# Logic_Module_V3.net
KiCad netlist of a schematic drawn in EAGLE
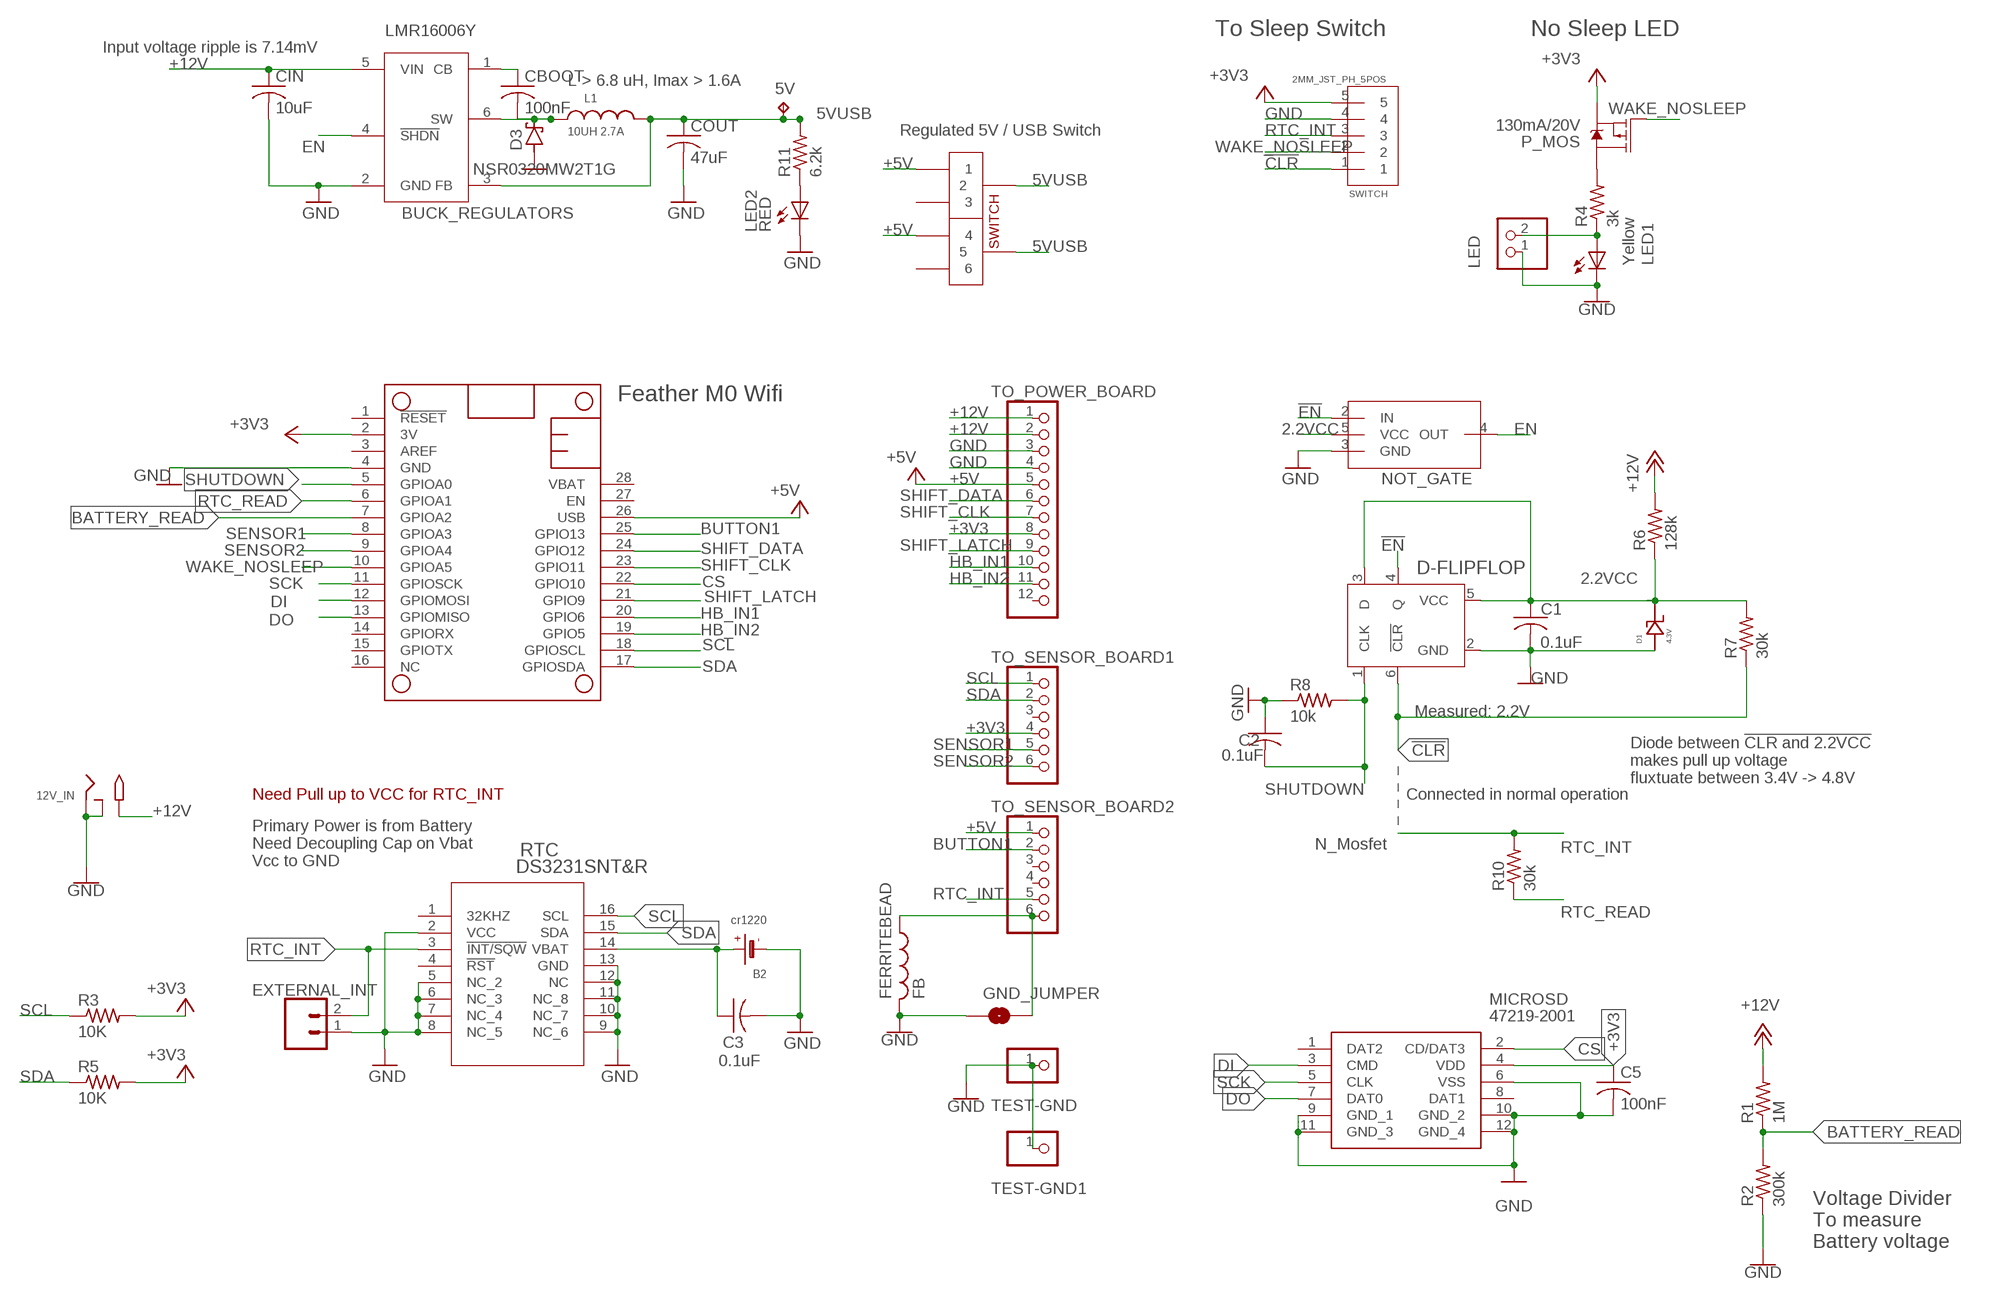
[diagram p0: schematic, sheet 1]

(export (version "E")
  (design (tool "Eeschema 10.0.6"))
  (components
    (comp (ref "5V")
      (value "TPTP16R")
      (footprint "eagle-import:TP16R")
      (libsource (lib "eagle-import") (part "TPTP16R"))
    )
    (comp (ref "12V_IN")
      (value "2.1MMJACKSMT")
      (footprint "eagle-import:DCJACK_2MM_SMT")
      (libsource (lib "eagle-import") (part "2.1MMJACKSMT"))
    )
    (comp (ref "B2")
      (value "cr1220")
      (footprint "eagle-import:CR1220-2")
      (libsource (lib "eagle-import") (part "BATTERYCR1220_2"))
    )
    (comp (ref "C1")
      (value "0.1uF")
      (footprint "eagle-import:C1206")
      (libsource (lib "eagle-import") (part "C-USC1206"))
    )
    (comp (ref "C2")
      (value "0.1uF")
      (footprint "eagle-import:C1206")
      (libsource (lib "eagle-import") (part "C-USC1206"))
    )
    (comp (ref "C3")
      (value "0.1uF")
      (footprint "eagle-import:C1206")
      (libsource (lib "eagle-import") (part "C-USC1206"))
    )
    (comp (ref "C5")
      (value "100nF")
      (footprint "eagle-import:C1206")
      (libsource (lib "eagle-import") (part "resistor_348_C-USC1206"))
    )
    (comp (ref "CBOOT")
      (value "100nF")
      (footprint "eagle-import:C1206")
      (libsource (lib "eagle-import") (part "rcl_334_C-USC1206"))
    )
    (comp (ref "CIN")
      (value "10uF")
      (footprint "eagle-import:C1206K")
      (libsource (lib "eagle-import") (part "rcl_334_C-USC1206K"))
    )
    (comp (ref "COUT")
      (value "47uF")
      (footprint "eagle-import:C1206")
      (libsource (lib "eagle-import") (part "rcl_334_C-USC1206"))
    )
    (comp (ref "D-FLIPFLOP")
      (value "SN74LVC1G175DBVR")
      (footprint "eagle-import:DBV6")
      (libsource (lib "eagle-import") (part "SN74LVC1G175DBVR"))
    )
    (comp (ref "D1")
      (value "4.3V")
      (footprint "eagle-import:DO-219AC")
      (libsource (lib "eagle-import") (part "ZENER-DO219"))
    )
    (comp (ref "D3")
      (value "NSR0320MW2T1G")
      (footprint "eagle-import:SOD323_ST")
      (libsource (lib "eagle-import") (part "BAT60J"))
    )
    (comp (ref "EXTERNAL_INT")
      (value "CONN_021X02_NO_SILK")
      (footprint "eagle-import:1X02_NO_SILK")
      (libsource (lib "eagle-import") (part "CONN_021X02_NO_SILK"))
    )
    (comp (ref "FERRITEBEAD")
      (value "FB")
      (footprint "eagle-import:FB")
      (libsource (lib "eagle-import") (part "FB"))
    )
    (comp (ref "GND_JUMPER")
      (value "JUMPER-SMT_2_NO_NO-SILK")
      (footprint "eagle-import:SMT-JUMPER_2_NO_NO-SILK")
      (libsource (lib "eagle-import") (part "JUMPER-SMT_2_NO_NO-SILK"))
    )
    (comp (ref "L1")
      (value "10UH 2.7A")
      (footprint "eagle-import:WE-MAPI_40XX")
      (libsource (lib "eagle-import") (part "WE-MAPI_4030_74438357100"))
    )
    (comp (ref "LED")
      (value "2.5MM_JST_UP_2POS")
      (footprint "eagle-import:JST_2POS_2.5MM_UP")
      (libsource (lib "eagle-import") (part "2.5MM_JST_UP_2POS"))
    )
    (comp (ref "LED1")
      (value "Yellow")
      (footprint "eagle-import:CHIPLED_0805")
      (libsource (lib "eagle-import") (part "LEDCHIPLED_0805"))
    )
    (comp (ref "LED2")
      (value "RED")
      (footprint "eagle-import:CHIPLED_0805")
      (libsource (lib "eagle-import") (part "LEDCHIPLED_0805"))
    )
    (comp (ref "MICROSD")
      (value "47219-2001")
      (footprint "eagle-import:472192001")
      (fields (field (name "MOUSER_PART_NUMBER") "538-47219-2001"))
      (libsource (lib "eagle-import") (part "47219-2001"))
    )
    (comp (ref "MS1")
      (value "FEATHERWING")
      (footprint "eagle-import:FEATHERWING")
      (libsource (lib "eagle-import") (part "FEATHERWING"))
    )
    (comp (ref "P_MOS")
      (value "130mA/20V")
      (footprint "eagle-import:SOT23-3")
      (libsource (lib "eagle-import") (part "MOSFET_PCH-IRLML2244"))
    )
    (comp (ref "R1")
      (value "1M")
      (footprint "eagle-import:R1206")
      (libsource (lib "eagle-import") (part "R-US_R1206"))
    )
    (comp (ref "R2")
      (value "300k")
      (footprint "eagle-import:R1206")
      (libsource (lib "eagle-import") (part "R-US_R1206"))
    )
    (comp (ref "R3")
      (value "10K")
      (footprint "eagle-import:R1206")
      (libsource (lib "eagle-import") (part "rcl_334_R-US_R1206"))
    )
    (comp (ref "R4")
      (value "3k")
      (footprint "eagle-import:R1206")
      (libsource (lib "eagle-import") (part "resistor_348_R-US_R1206"))
    )
    (comp (ref "R5")
      (value "10K")
      (footprint "eagle-import:R1206")
      (libsource (lib "eagle-import") (part "rcl_334_R-US_R1206"))
    )
    (comp (ref "R6")
      (value "128k")
      (footprint "eagle-import:R1206")
      (libsource (lib "eagle-import") (part "R-US_R1206"))
    )
    (comp (ref "R7")
      (value "30k")
      (footprint "eagle-import:R1206")
      (libsource (lib "eagle-import") (part "R-US_R1206"))
    )
    (comp (ref "R8")
      (value "10k")
      (footprint "eagle-import:R1206")
      (libsource (lib "eagle-import") (part "R-US_R1206"))
    )
    (comp (ref "R10")
      (value "30k")
      (footprint "eagle-import:R1206")
      (libsource (lib "eagle-import") (part "R-US_R1206"))
    )
    (comp (ref "R11")
      (value "6.2k")
      (footprint "eagle-import:RES_1206")
      (fields
        (field (name "DIGIKEY_PART_NUMBER") "WSLP-.05TR-ND")
        (field (name "MANUFACTURER") "Vishay Dale")
        (field (name "MPN") "WSLP1206R0500FEA")
        (field (name "CREATED_BY") "PCBLayout.com")
      )
      (libsource (lib "eagle-import") (part "WSLP1206R0500FEA"))
    )
    (comp (ref "RTC")
      (value "DS3231SNT&R")
      (footprint "eagle-import:21-0042B_16")
      (fields (field (name "MANUFACTURER_PART_NUMBER") "DS3231SN#T&R"))
      (libsource (lib "eagle-import") (part "DS3231SNT&R"))
    )
    (comp (ref "SWITCH")
      (value "2MM_JST_PH_5POS")
      (footprint "eagle-import:2MM_5POS_HEADER")
      (libsource (lib "eagle-import") (part "2MM_JST_PH_5POS"))
    )
    (comp (ref "TEST-GND")
      (value "PINHD-1X1")
      (footprint "eagle-import:1X01")
      (libsource (lib "eagle-import") (part "PINHD-1X1"))
    )
    (comp (ref "TEST-GND1")
      (value "PINHD-1X1")
      (footprint "eagle-import:1X01")
      (libsource (lib "eagle-import") (part "PINHD-1X1"))
    )
    (comp (ref "TO_POWER_BOARD")
      (value "PINHD-1X12")
      (footprint "eagle-import:1X12")
      (libsource (lib "eagle-import") (part "PINHD-1X12"))
    )
    (comp (ref "TO_SENSOR_BOARD1")
      (value "PINHD-1X6CB")
      (footprint "eagle-import:1X06-CLEANBIG")
      (libsource (lib "eagle-import") (part "PINHD-1X6CB"))
    )
    (comp (ref "TO_SENSOR_BOARD2")
      (value "PINHD-1X6CB")
      (footprint "eagle-import:1X06-CLEANBIG")
      (libsource (lib "eagle-import") (part "PINHD-1X6CB"))
    )
    (comp (ref "U$1")
      (value "2PDT_SWITCHJS-SMD")
      (footprint "eagle-import:JS-DPDT-SMD")
      (libsource (lib "eagle-import") (part "2PDT_SWITCHJS-SMD"))
    )
    (comp (ref "U$3")
      (value "NOT_GATE")
      (footprint "eagle-import:SOT753")
      (libsource (lib "eagle-import") (part "NOT_GATE"))
    )
    (comp (ref "VREG")
      (value "BUCK_REGULATORS")
      (footprint "eagle-import:SOT23-6")
      (libsource (lib "eagle-import") (part "BUCK_REGULATORS"))
    )
  )
  (nets
    (net (code "1") (name "+3V3") (class "Default")
      (node (ref "C5") (pin "1") (pinfunction "1_1") (pintype "passive"))
      (node (ref "MICROSD") (pin "4") (pinfunction "VDD_4") (pintype "bidirectional"))
      (node (ref "MS1") (pin "2") (pinfunction "3V_2") (pintype "power_in"))
      (node (ref "P_MOS") (pin "2") (pinfunction "S_2") (pintype "bidirectional"))
      (node (ref "R3") (pin "2") (pinfunction "2_2") (pintype "passive"))
      (node (ref "R5") (pin "2") (pinfunction "2_2") (pintype "passive"))
      (node (ref "SWITCH") (pin "5") (pinfunction "5_5") (pintype "bidirectional"))
      (node (ref "TO_POWER_BOARD") (pin "8") (pinfunction "8_8") (pintype "passive"))
      (node (ref "TO_SENSOR_BOARD1") (pin "4") (pinfunction "4_4") (pintype "passive"))
    )
    (net (code "2") (name "+5V") (class "Default")
      (node (ref "MS1") (pin "26") (pinfunction "USB_26") (pintype "power_in"))
      (node (ref "TO_POWER_BOARD") (pin "5") (pinfunction "5_5") (pintype "passive"))
      (node (ref "TO_SENSOR_BOARD2") (pin "1") (pinfunction "1_1") (pintype "passive"))
      (node (ref "U$1") (pin "P$1") (pinfunction "1_P$1") (pintype "bidirectional"))
      (node (ref "U$1") (pin "P$4") (pinfunction "4_P$4") (pintype "bidirectional"))
    )
    (net (code "3") (name "+12V") (class "Default")
      (node (ref "12V_IN") (pin "PWR2") (pinfunction "TIP_PWR2") (pintype "bidirectional"))
      (node (ref "CIN") (pin "1") (pinfunction "1_1") (pintype "passive"))
      (node (ref "R1") (pin "2") (pinfunction "2_2") (pintype "passive"))
      (node (ref "R6") (pin "2") (pinfunction "2_2") (pintype "passive"))
      (node (ref "TO_POWER_BOARD") (pin "1") (pinfunction "1_1") (pintype "passive"))
      (node (ref "TO_POWER_BOARD") (pin "2") (pinfunction "2_2") (pintype "passive"))
      (node (ref "VREG") (pin "5") (pinfunction "VIN_5") (pintype "bidirectional"))
    )
    (net (code "4") (name "/2.2VCC") (class "Default")
      (node (ref "C1") (pin "1") (pinfunction "1_1") (pintype "passive"))
      (node (ref "D-FLIPFLOP") (pin "3") (pinfunction "D_3") (pintype "input"))
      (node (ref "D-FLIPFLOP") (pin "5") (pinfunction "VCC_5") (pintype "power_in"))
      (node (ref "D1") (pin "FNT") (pinfunction "FNT_FNT") (pintype "bidirectional"))
      (node (ref "R6") (pin "1") (pinfunction "1_1") (pintype "passive"))
      (node (ref "R7") (pin "2") (pinfunction "2_2") (pintype "passive"))
      (node (ref "U$3") (pin "5") (pinfunction "VCC_5") (pintype "bidirectional"))
    )
    (net (code "5") (name "/5VUSB") (class "Default")
      (node (ref "5V") (pin "TP") (pinfunction "TP_TP") (pintype "input"))
      (node (ref "COUT") (pin "1") (pinfunction "1_1") (pintype "passive"))
      (node (ref "L1") (pin "2") (pinfunction "2_2") (pintype "passive"))
      (node (ref "R11") (pin "2") (pinfunction "2_2") (pintype "passive"))
      (node (ref "U$1") (pin "P$2") (pinfunction "2_P$2") (pintype "bidirectional"))
      (node (ref "U$1") (pin "P$5") (pinfunction "5_P$5") (pintype "bidirectional"))
      (node (ref "VREG") (pin "3") (pinfunction "FB_3") (pintype "bidirectional"))
    )
    (net (code "6") (name "/BUTTON1") (class "Default")
      (node (ref "MS1") (pin "25") (pinfunction "GPIO13_25") (pintype "bidirectional"))
      (node (ref "TO_SENSOR_BOARD2") (pin "2") (pinfunction "2_2") (pintype "passive"))
    )
    (net (code "7") (name "/EN") (class "Default")
      (node (ref "U$3") (pin "4") (pinfunction "OUT_4") (pintype "bidirectional"))
      (node (ref "VREG") (pin "4") (pinfunction "~{SHDN}_4") (pintype "bidirectional"))
    )
    (net (code "8") (name "/HB_IN1") (class "Default")
      (node (ref "MS1") (pin "20") (pinfunction "GPIO6_20") (pintype "bidirectional"))
      (node (ref "TO_POWER_BOARD") (pin "10") (pinfunction "10_10") (pintype "passive"))
    )
    (net (code "9") (name "/HB_IN2") (class "Default")
      (node (ref "MS1") (pin "19") (pinfunction "GPIO5_19") (pintype "bidirectional"))
      (node (ref "TO_POWER_BOARD") (pin "11") (pinfunction "11_11") (pintype "passive"))
    )
    (net (code "10") (name "/SENSOR1") (class "Default")
      (node (ref "MS1") (pin "8") (pinfunction "GPIOA3_8") (pintype "bidirectional"))
      (node (ref "TO_SENSOR_BOARD1") (pin "5") (pinfunction "5_5") (pintype "passive"))
    )
    (net (code "11") (name "/SENSOR2") (class "Default")
      (node (ref "MS1") (pin "9") (pinfunction "GPIOA4_9") (pintype "bidirectional"))
      (node (ref "TO_SENSOR_BOARD1") (pin "6") (pinfunction "6_6") (pintype "passive"))
    )
    (net (code "12") (name "/SHIFT_CLK") (class "Default")
      (node (ref "MS1") (pin "23") (pinfunction "GPIO11_23") (pintype "bidirectional"))
      (node (ref "TO_POWER_BOARD") (pin "7") (pinfunction "7_7") (pintype "passive"))
    )
    (net (code "13") (name "/SHIFT_DATA") (class "Default")
      (node (ref "MS1") (pin "24") (pinfunction "GPIO12_24") (pintype "bidirectional"))
      (node (ref "TO_POWER_BOARD") (pin "6") (pinfunction "6_6") (pintype "passive"))
    )
    (net (code "14") (name "/SHIFT_LATCH") (class "Default")
      (node (ref "MS1") (pin "21") (pinfunction "GPIO9_21") (pintype "bidirectional"))
      (node (ref "TO_POWER_BOARD") (pin "9") (pinfunction "9_9") (pintype "passive"))
    )
    (net (code "15") (name "/VBAT") (class "Default")
      (node (ref "MS1") (pin "28") (pinfunction "VBAT_28") (pintype "power_in"))
    )
    (net (code "16") (name "/WAKE_NOSLEEP") (class "Default")
      (node (ref "MS1") (pin "10") (pinfunction "GPIOA5_10") (pintype "bidirectional"))
      (node (ref "P_MOS") (pin "1") (pinfunction "G_1") (pintype "bidirectional"))
      (node (ref "SWITCH") (pin "2") (pinfunction "2_2") (pintype "bidirectional"))
    )
    (net (code "17") (name "/~{CLR}") (class "Default")
      (node (ref "D-FLIPFLOP") (pin "6") (pinfunction "~{CLR}_6") (pintype "input"))
      (node (ref "R7") (pin "1") (pinfunction "1_1") (pintype "passive"))
      (node (ref "SWITCH") (pin "1") (pinfunction "1_1") (pintype "bidirectional"))
    )
    (net (code "18") (name "/~{EN}") (class "Default")
      (node (ref "D-FLIPFLOP") (pin "4") (pinfunction "Q_4") (pintype "output"))
      (node (ref "U$3") (pin "2") (pinfunction "IN_2") (pintype "bidirectional"))
    )
    (net (code "19") (name "BATTERY_READ") (class "Default")
      (node (ref "MS1") (pin "7") (pinfunction "GPIOA2_7") (pintype "bidirectional"))
      (node (ref "R1") (pin "1") (pinfunction "1_1") (pintype "passive"))
      (node (ref "R2") (pin "2") (pinfunction "2_2") (pintype "passive"))
    )
    (net (code "20") (name "CS") (class "Default")
      (node (ref "MICROSD") (pin "2") (pinfunction "CD/DAT3_2") (pintype "bidirectional"))
      (node (ref "MS1") (pin "22") (pinfunction "GPIO10_22") (pintype "bidirectional"))
    )
    (net (code "21") (name "DI") (class "Default")
      (node (ref "MICROSD") (pin "3") (pinfunction "CMD_3") (pintype "bidirectional"))
      (node (ref "MS1") (pin "12") (pinfunction "GPIOMOSI_12") (pintype "bidirectional"))
    )
    (net (code "22") (name "DO") (class "Default")
      (node (ref "MICROSD") (pin "7") (pinfunction "DAT0_7") (pintype "bidirectional"))
      (node (ref "MS1") (pin "13") (pinfunction "GPIOMISO_13") (pintype "bidirectional"))
    )
    (net (code "23") (name "GND") (class "Default")
      (node (ref "12V_IN") (pin "GND") (pinfunction "RING_GND") (pintype "bidirectional"))
      (node (ref "12V_IN") (pin "GNDBREAK") (pinfunction "RING_SW_GNDBREAK") (pintype "bidirectional"))
      (node (ref "B2") (pin "-") (pinfunction "-_-") (pintype "passive"))
      (node (ref "C1") (pin "2") (pinfunction "2_2") (pintype "passive"))
      (node (ref "C2") (pin "1") (pinfunction "1_1") (pintype "passive"))
      (node (ref "C3") (pin "2") (pinfunction "2_2") (pintype "passive"))
      (node (ref "C5") (pin "2") (pinfunction "2_2") (pintype "passive"))
      (node (ref "CIN") (pin "2") (pinfunction "2_2") (pintype "passive"))
      (node (ref "COUT") (pin "2") (pinfunction "2_2") (pintype "passive"))
      (node (ref "D-FLIPFLOP") (pin "2") (pinfunction "GND_2") (pintype "power_in"))
      (node (ref "D1") (pin "BCK") (pinfunction "BCK_BCK") (pintype "bidirectional"))
      (node (ref "D3") (pin "A") (pinfunction "A_A") (pintype "passive"))
      (node (ref "EXTERNAL_INT") (pin "1") (pinfunction "1_1") (pintype "passive"))
      (node (ref "FERRITEBEAD") (pin "P$2") (pinfunction "2_P$2") (pintype "passive"))
      (node (ref "GND_JUMPER") (pin "1") (pinfunction "1_1") (pintype "passive"))
      (node (ref "LED") (pin "1") (pinfunction "1_1") (pintype "bidirectional"))
      (node (ref "LED1") (pin "C") (pinfunction "C_C") (pintype "passive"))
      (node (ref "LED2") (pin "C") (pinfunction "C_C") (pintype "passive"))
      (node (ref "MICROSD") (pin "10") (pinfunction "GND_2_10") (pintype "bidirectional"))
      (node (ref "MICROSD") (pin "11") (pinfunction "GND_3_11") (pintype "bidirectional"))
      (node (ref "MICROSD") (pin "12") (pinfunction "GND_4_12") (pintype "bidirectional"))
      (node (ref "MICROSD") (pin "6") (pinfunction "VSS_6") (pintype "bidirectional"))
      (node (ref "MICROSD") (pin "9") (pinfunction "GND_1_9") (pintype "bidirectional"))
      (node (ref "MS1") (pin "4") (pinfunction "GND_4") (pintype "power_in"))
      (node (ref "R2") (pin "1") (pinfunction "1_1") (pintype "passive"))
      (node (ref "R8") (pin "1") (pinfunction "1_1") (pintype "passive"))
      (node (ref "RTC") (pin "10") (pinfunction "NC_7_10") (pintype "passive"))
      (node (ref "RTC") (pin "11") (pinfunction "NC_8_11") (pintype "passive"))
      (node (ref "RTC") (pin "12") (pinfunction "NC_12") (pintype "passive"))
      (node (ref "RTC") (pin "13") (pinfunction "GND_13") (pintype "power_in"))
      (node (ref "RTC") (pin "2") (pinfunction "VCC_2") (pintype "power_in"))
      (node (ref "RTC") (pin "5") (pinfunction "NC_2_5") (pintype "passive"))
      (node (ref "RTC") (pin "6") (pinfunction "NC_3_6") (pintype "passive"))
      (node (ref "RTC") (pin "7") (pinfunction "NC_4_7") (pintype "passive"))
      (node (ref "RTC") (pin "8") (pinfunction "NC_5_8") (pintype "passive"))
      (node (ref "RTC") (pin "9") (pinfunction "NC_6_9") (pintype "passive"))
      (node (ref "SWITCH") (pin "4") (pinfunction "4_4") (pintype "bidirectional"))
      (node (ref "TEST-GND") (pin "1") (pinfunction "1_1") (pintype "passive"))
      (node (ref "TEST-GND1") (pin "1") (pinfunction "1_1") (pintype "passive"))
      (node (ref "TO_POWER_BOARD") (pin "3") (pinfunction "3_3") (pintype "passive"))
      (node (ref "TO_POWER_BOARD") (pin "4") (pinfunction "4_4") (pintype "passive"))
      (node (ref "U$3") (pin "3") (pinfunction "GND_3") (pintype "bidirectional"))
      (node (ref "VREG") (pin "2") (pinfunction "GND_2") (pintype "bidirectional"))
    )
    (net (code "24") (name "Net-(FERRITEBEAD-1)") (class "Default")
      (node (ref "FERRITEBEAD") (pin "P$1") (pinfunction "1_P$1") (pintype "passive"))
      (node (ref "GND_JUMPER") (pin "2") (pinfunction "2_2") (pintype "passive"))
      (node (ref "TO_SENSOR_BOARD2") (pin "6") (pinfunction "6_6") (pintype "passive"))
    )
    (net (code "25") (name "Net-(LED-Pad2)") (class "Default")
      (node (ref "LED") (pin "2") (pinfunction "2_2") (pintype "bidirectional"))
      (node (ref "LED1") (pin "A") (pinfunction "A_A") (pintype "passive"))
      (node (ref "R4") (pin "1") (pinfunction "1_1") (pintype "passive"))
    )
    (net (code "26") (name "Net-(LED2-PadA)") (class "Default")
      (node (ref "LED2") (pin "A") (pinfunction "A_A") (pintype "passive"))
      (node (ref "R11") (pin "1") (pinfunction "1_1") (pintype "passive"))
    )
    (net (code "27") (name "Net-(P_MOS-D)") (class "Default")
      (node (ref "P_MOS") (pin "3") (pinfunction "D_3") (pintype "bidirectional"))
      (node (ref "R4") (pin "2") (pinfunction "2_2") (pintype "passive"))
    )
    (net (code "28") (name "Net-(RTC-VBAT)") (class "Default")
      (node (ref "B2") (pin "+") (pinfunction "+_+") (pintype "passive"))
      (node (ref "C3") (pin "1") (pinfunction "1_1") (pintype "passive"))
      (node (ref "RTC") (pin "14") (pinfunction "VBAT_14") (pintype "power_in"))
    )
    (net (code "29") (name "Net-(VREG-CB)") (class "Default")
      (node (ref "CBOOT") (pin "1") (pinfunction "1_1") (pintype "passive"))
      (node (ref "VREG") (pin "1") (pinfunction "CB_1") (pintype "bidirectional"))
    )
    (net (code "30") (name "Net-(VREG-SW)") (class "Default")
      (node (ref "CBOOT") (pin "2") (pinfunction "2_2") (pintype "passive"))
      (node (ref "D3") (pin "C") (pinfunction "C_C") (pintype "passive"))
      (node (ref "L1") (pin "1") (pinfunction "1_1") (pintype "passive"))
      (node (ref "VREG") (pin "6") (pinfunction "SW_6") (pintype "bidirectional"))
    )
    (net (code "31") (name "RTC_INT") (class "Default")
      (node (ref "EXTERNAL_INT") (pin "2") (pinfunction "2_2") (pintype "passive"))
      (node (ref "R10") (pin "2") (pinfunction "2_2") (pintype "passive"))
      (node (ref "RTC") (pin "3") (pinfunction "~{INT/SQW}_3") (pintype "passive"))
      (node (ref "SWITCH") (pin "3") (pinfunction "3_3") (pintype "bidirectional"))
      (node (ref "TO_SENSOR_BOARD2") (pin "5") (pinfunction "5_5") (pintype "passive"))
    )
    (net (code "32") (name "RTC_READ") (class "Default")
      (node (ref "MS1") (pin "6") (pinfunction "GPIOA1_6") (pintype "bidirectional"))
      (node (ref "R10") (pin "1") (pinfunction "1_1") (pintype "passive"))
    )
    (net (code "33") (name "SCK") (class "Default")
      (node (ref "MICROSD") (pin "5") (pinfunction "CLK_5") (pintype "bidirectional"))
      (node (ref "MS1") (pin "11") (pinfunction "GPIOSCK_11") (pintype "bidirectional"))
    )
    (net (code "34") (name "SCL") (class "Default")
      (node (ref "MS1") (pin "18") (pinfunction "GPIOSCL_18") (pintype "bidirectional"))
      (node (ref "R3") (pin "1") (pinfunction "1_1") (pintype "passive"))
      (node (ref "RTC") (pin "16") (pinfunction "SCL_16") (pintype "passive"))
      (node (ref "TO_SENSOR_BOARD1") (pin "1") (pinfunction "1_1") (pintype "passive"))
    )
    (net (code "35") (name "SDA") (class "Default")
      (node (ref "MS1") (pin "17") (pinfunction "GPIOSDA_17") (pintype "bidirectional"))
      (node (ref "R5") (pin "1") (pinfunction "1_1") (pintype "passive"))
      (node (ref "RTC") (pin "15") (pinfunction "SDA_15") (pintype "passive"))
      (node (ref "TO_SENSOR_BOARD1") (pin "2") (pinfunction "2_2") (pintype "passive"))
    )
    (net (code "36") (name "SHUTDOWN") (class "Default")
      (node (ref "C2") (pin "2") (pinfunction "2_2") (pintype "passive"))
      (node (ref "D-FLIPFLOP") (pin "1") (pinfunction "CLK_1") (pintype "input"))
      (node (ref "MS1") (pin "5") (pinfunction "GPIOA0_5") (pintype "bidirectional"))
      (node (ref "R8") (pin "2") (pinfunction "2_2") (pintype "passive"))
    )
    (net (code "37") (name "unconnected-(MICROSD-DAT1-Pad8)") (class "Default")
      (node (ref "MICROSD") (pin "8") (pinfunction "DAT1_8") (pintype "bidirectional"))
    )
    (net (code "38") (name "unconnected-(MICROSD-DAT2-Pad1)") (class "Default")
      (node (ref "MICROSD") (pin "1") (pinfunction "DAT2_1") (pintype "bidirectional"))
    )
    (net (code "39") (name "unconnected-(MS1-AREF-Pad3)") (class "Default")
      (node (ref "MS1") (pin "3") (pinfunction "AREF_3") (pintype "passive"))
    )
    (net (code "40") (name "unconnected-(MS1-EN-Pad27)") (class "Default")
      (node (ref "MS1") (pin "27") (pinfunction "EN_27") (pintype "passive"))
    )
    (net (code "41") (name "unconnected-(MS1-GPIORX-Pad14)") (class "Default")
      (node (ref "MS1") (pin "14") (pinfunction "GPIORX_14") (pintype "bidirectional"))
    )
    (net (code "42") (name "unconnected-(MS1-GPIOTX-Pad15)") (class "Default")
      (node (ref "MS1") (pin "15") (pinfunction "GPIOTX_15") (pintype "bidirectional"))
    )
    (net (code "43") (name "unconnected-(MS1-NC-Pad16)") (class "Default")
      (node (ref "MS1") (pin "16") (pinfunction "NC_16") (pintype "passive"))
    )
    (net (code "44") (name "unconnected-(MS1-~{RESET}-Pad1)") (class "Default")
      (node (ref "MS1") (pin "1") (pinfunction "~{RESET}_1") (pintype "input"))
    )
    (net (code "45") (name "unconnected-(RTC-32KHZ-Pad1)") (class "Default")
      (node (ref "RTC") (pin "1") (pinfunction "32KHZ_1") (pintype "passive"))
    )
    (net (code "46") (name "unconnected-(RTC-~{RST}-Pad4)") (class "Default")
      (node (ref "RTC") (pin "4") (pinfunction "~{RST}_4") (pintype "passive"))
    )
    (net (code "47") (name "unconnected-(TO_POWER_BOARD-Pad12)") (class "Default")
      (node (ref "TO_POWER_BOARD") (pin "12") (pinfunction "12_12") (pintype "passive"))
    )
    (net (code "48") (name "unconnected-(TO_SENSOR_BOARD1-Pad3)") (class "Default")
      (node (ref "TO_SENSOR_BOARD1") (pin "3") (pinfunction "3_3") (pintype "passive"))
    )
    (net (code "49") (name "unconnected-(TO_SENSOR_BOARD2-Pad3)") (class "Default")
      (node (ref "TO_SENSOR_BOARD2") (pin "3") (pinfunction "3_3") (pintype "passive"))
    )
    (net (code "50") (name "unconnected-(TO_SENSOR_BOARD2-Pad4)") (class "Default")
      (node (ref "TO_SENSOR_BOARD2") (pin "4") (pinfunction "4_4") (pintype "passive"))
    )
    (net (code "51") (name "unconnected-(U$1-3-PadP$3)") (class "Default")
      (node (ref "U$1") (pin "P$3") (pinfunction "3_P$3") (pintype "bidirectional"))
    )
    (net (code "52") (name "unconnected-(U$1-6-PadP$6)") (class "Default")
      (node (ref "U$1") (pin "P$6") (pinfunction "6_P$6") (pintype "bidirectional"))
    )
  )
)
